# ThermocoupleADC.net
KiCad netlist of a schematic drawn in Altium Designer
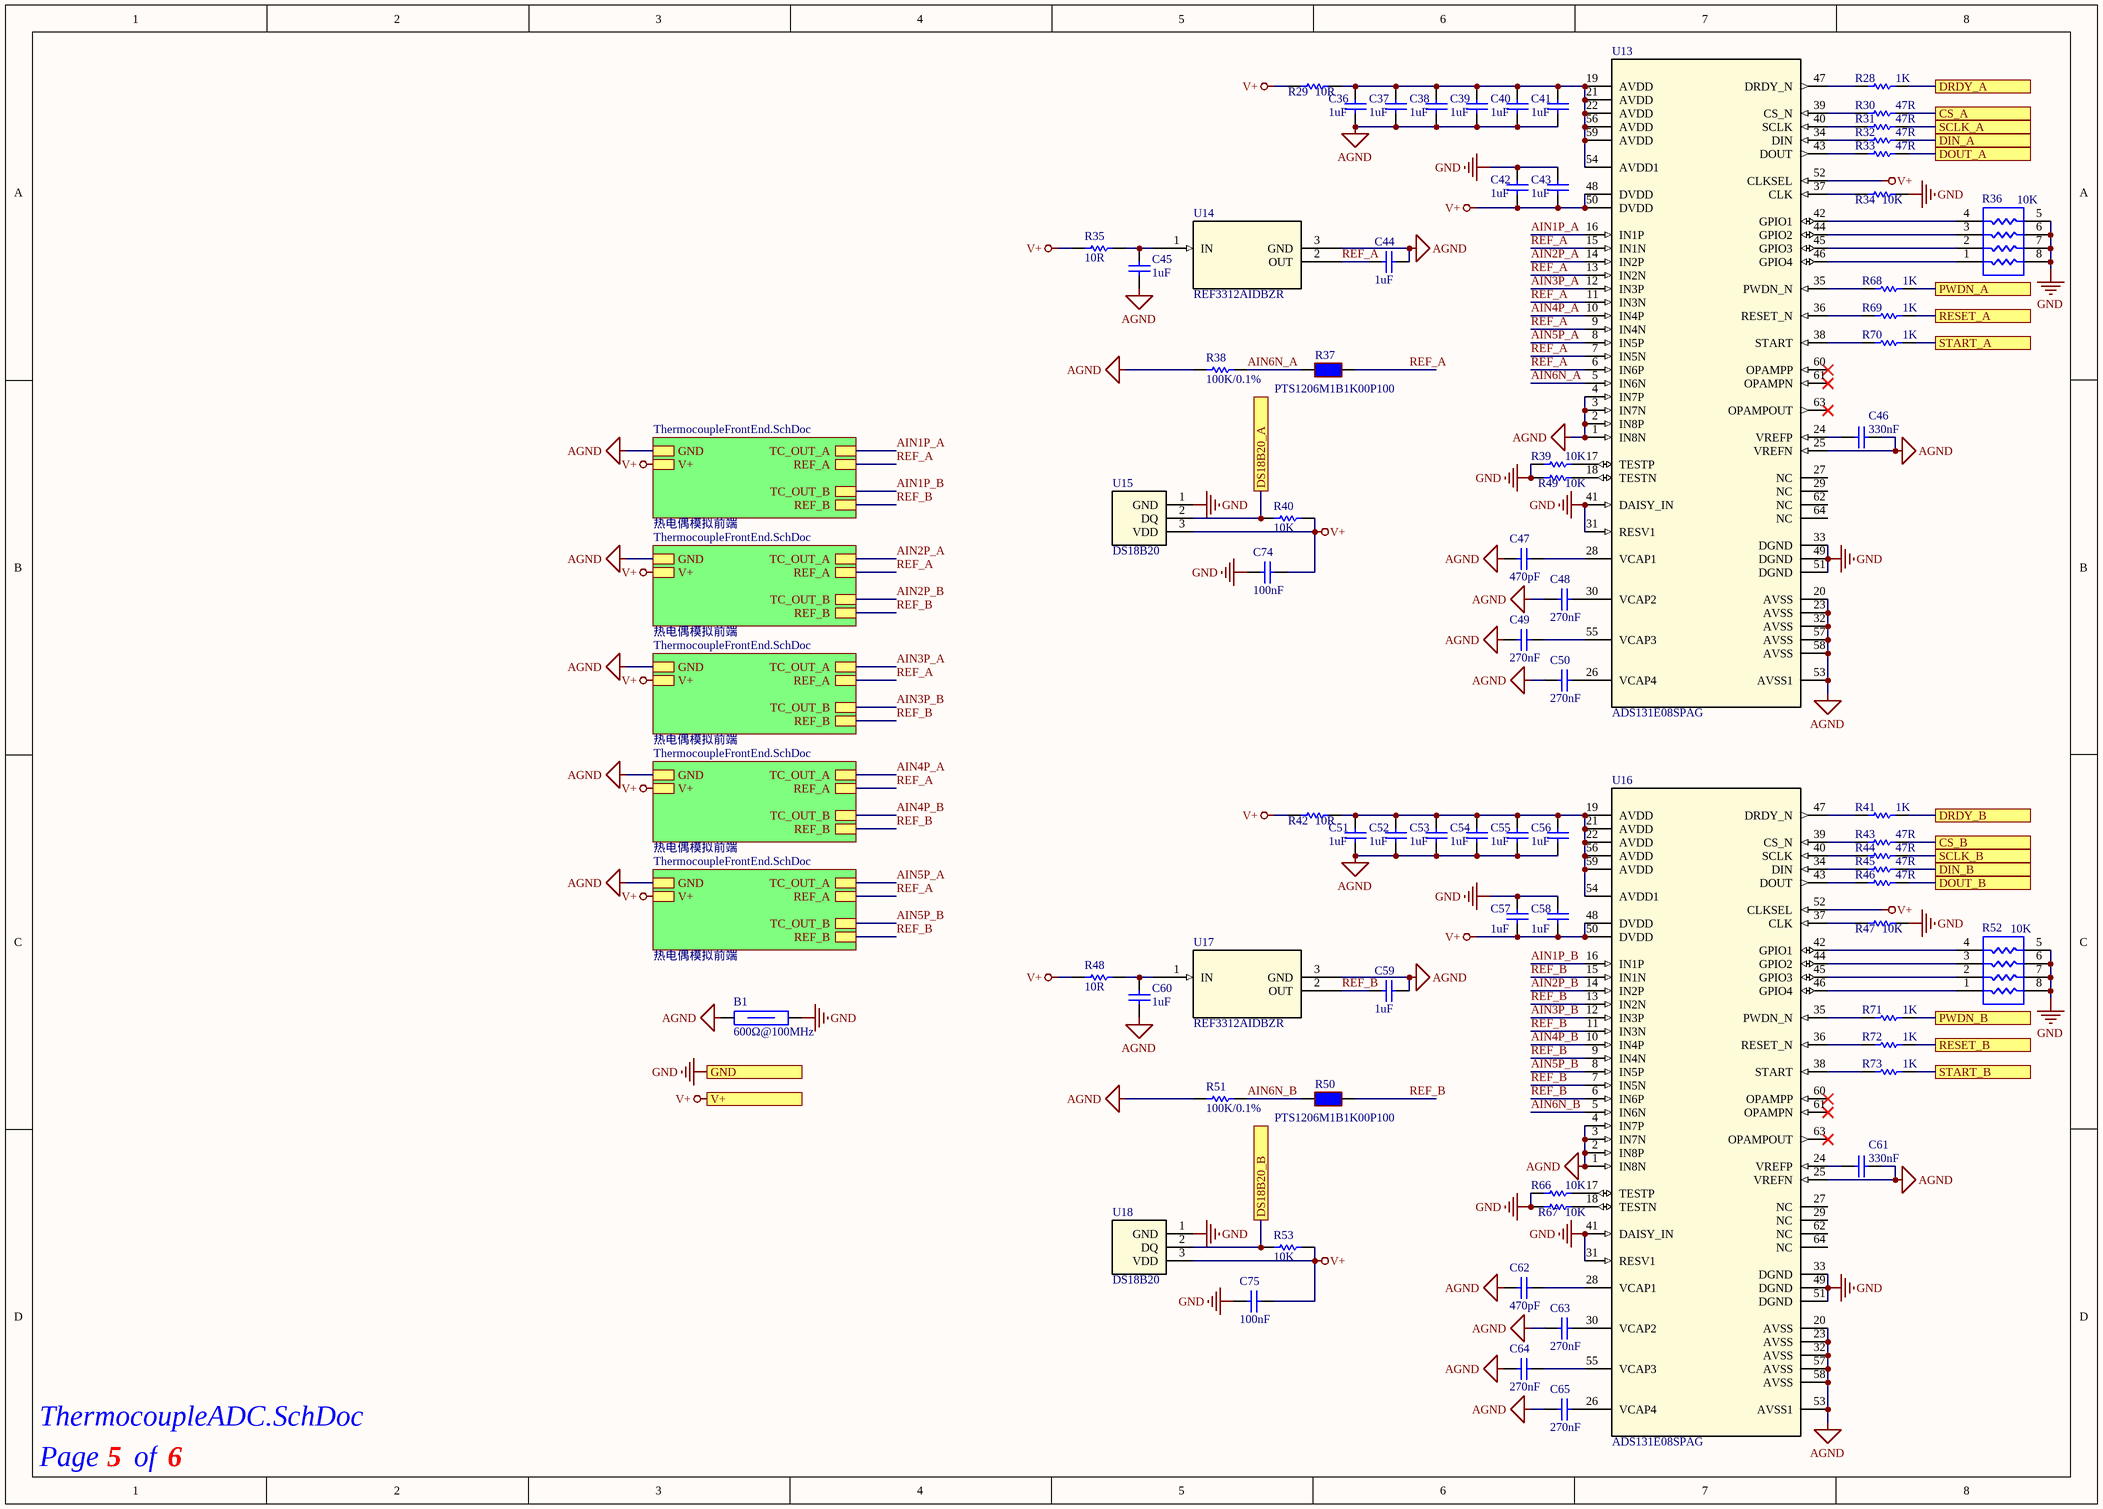
[diagram p0: ThermocoupleADC.SchDoc]

(export (version "E")
  (design (tool "Eeschema 10.0.6"))
  (components
    (comp (ref "B1")
      (value "600Ω@100MHz")
      (footprint "R0805_L")
      (description "600Ω @ 100MHz \r\n线路数 1 \r\n额定电流（最大） 600mA \r\n直流电阻（DCR）（最大） 210mΩ")
      (libsource (lib "00Lib") (part "600Ω@100MHz"))
    )
    (comp (ref "C36")
      (value "1uF")
      (footprint "R0603_C")
      (description "精度 ±10% \r\n容值 1uF \r\n额定电压 50V \r\n温漂系数（介质材料) X7R")
      (libsource (lib "00Lib") (part "1uF/0603/50V"))
    )
    (comp (ref "C37")
      (value "1uF")
      (footprint "R0603_C")
      (description "精度 ±10% \r\n容值 1uF \r\n额定电压 50V \r\n温漂系数（介质材料) X7R")
      (libsource (lib "00Lib") (part "1uF/0603/50V"))
    )
    (comp (ref "C38")
      (value "1uF")
      (footprint "R0603_C")
      (description "精度 ±10% \r\n容值 1uF \r\n额定电压 50V \r\n温漂系数（介质材料) X7R")
      (libsource (lib "00Lib") (part "1uF/0603/50V"))
    )
    (comp (ref "C39")
      (value "1uF")
      (footprint "R0603_C")
      (description "精度 ±10% \r\n容值 1uF \r\n额定电压 50V \r\n温漂系数（介质材料) X7R")
      (libsource (lib "00Lib") (part "1uF/0603/50V"))
    )
    (comp (ref "C40")
      (value "1uF")
      (footprint "R0603_C")
      (description "精度 ±10% \r\n容值 1uF \r\n额定电压 50V \r\n温漂系数（介质材料) X7R")
      (libsource (lib "00Lib") (part "1uF/0603/50V"))
    )
    (comp (ref "C41")
      (value "1uF")
      (footprint "R0603_C")
      (description "精度 ±10% \r\n容值 1uF \r\n额定电压 50V \r\n温漂系数（介质材料) X7R")
      (libsource (lib "00Lib") (part "1uF/0603/50V"))
    )
    (comp (ref "C42")
      (value "1uF")
      (footprint "R0603_C")
      (description "精度 ±10% \r\n容值 1uF \r\n额定电压 50V \r\n温漂系数（介质材料) X7R")
      (libsource (lib "00Lib") (part "1uF/0603/50V"))
    )
    (comp (ref "C43")
      (value "1uF")
      (footprint "R0603_C")
      (description "精度 ±10% \r\n容值 1uF \r\n额定电压 50V \r\n温漂系数（介质材料) X7R")
      (libsource (lib "00Lib") (part "1uF/0603/50V"))
    )
    (comp (ref "C44")
      (value "1uF")
      (footprint "R0603_C")
      (description "精度 ±10% \r\n容值 1uF \r\n额定电压 50V \r\n温漂系数（介质材料) X7R")
      (libsource (lib "00Lib") (part "1uF/0603/50V"))
    )
    (comp (ref "C45")
      (value "1uF")
      (footprint "R0603_C")
      (description "精度 ±10% \r\n容值 1uF \r\n额定电压 50V \r\n温漂系数（介质材料) X7R")
      (libsource (lib "00Lib") (part "1uF/0603/50V"))
    )
    (comp (ref "C46")
      (value "330nF")
      (footprint "R0603_C")
      (description "精度 ±10% \r\n容值 330nF \r\n额定电压 25V \r\n温漂系数（介质材料) X7R")
      (libsource (lib "00Lib") (part "330nF/0603/25V"))
    )
    (comp (ref "C47")
      (value "470pF")
      (footprint "R0603_C")
      (description "精度 ±5% \r\n容值 470pF \r\n额定电压 50V \r\n温漂系数（介质材料) C0G")
      (libsource (lib "00Lib") (part "470pF/0603/50V"))
    )
    (comp (ref "C48")
      (value "270nF")
      (footprint "R0603_C")
      (description "精度 ±10% \r\n容值 270nF \r\n额定电压 50V \r\n温漂系数（介质材料) X7R")
      (libsource (lib "00Lib") (part "270nF/0603/50V"))
    )
    (comp (ref "C49")
      (value "270nF")
      (footprint "R0603_C")
      (description "精度 ±10% \r\n容值 270nF \r\n额定电压 50V \r\n温漂系数（介质材料) X7R")
      (libsource (lib "00Lib") (part "270nF/0603/50V"))
    )
    (comp (ref "C50")
      (value "270nF")
      (footprint "R0603_C")
      (description "精度 ±10% \r\n容值 270nF \r\n额定电压 50V \r\n温漂系数（介质材料) X7R")
      (libsource (lib "00Lib") (part "270nF/0603/50V"))
    )
    (comp (ref "C51")
      (value "1uF")
      (footprint "R0603_C")
      (description "精度 ±10% \r\n容值 1uF \r\n额定电压 50V \r\n温漂系数（介质材料) X7R")
      (libsource (lib "00Lib") (part "1uF/0603/50V"))
    )
    (comp (ref "C52")
      (value "1uF")
      (footprint "R0603_C")
      (description "精度 ±10% \r\n容值 1uF \r\n额定电压 50V \r\n温漂系数（介质材料) X7R")
      (libsource (lib "00Lib") (part "1uF/0603/50V"))
    )
    (comp (ref "C53")
      (value "1uF")
      (footprint "R0603_C")
      (description "精度 ±10% \r\n容值 1uF \r\n额定电压 50V \r\n温漂系数（介质材料) X7R")
      (libsource (lib "00Lib") (part "1uF/0603/50V"))
    )
    (comp (ref "C54")
      (value "1uF")
      (footprint "R0603_C")
      (description "精度 ±10% \r\n容值 1uF \r\n额定电压 50V \r\n温漂系数（介质材料) X7R")
      (libsource (lib "00Lib") (part "1uF/0603/50V"))
    )
    (comp (ref "C55")
      (value "1uF")
      (footprint "R0603_C")
      (description "精度 ±10% \r\n容值 1uF \r\n额定电压 50V \r\n温漂系数（介质材料) X7R")
      (libsource (lib "00Lib") (part "1uF/0603/50V"))
    )
    (comp (ref "C56")
      (value "1uF")
      (footprint "R0603_C")
      (description "精度 ±10% \r\n容值 1uF \r\n额定电压 50V \r\n温漂系数（介质材料) X7R")
      (libsource (lib "00Lib") (part "1uF/0603/50V"))
    )
    (comp (ref "C57")
      (value "1uF")
      (footprint "R0603_C")
      (description "精度 ±10% \r\n容值 1uF \r\n额定电压 50V \r\n温漂系数（介质材料) X7R")
      (libsource (lib "00Lib") (part "1uF/0603/50V"))
    )
    (comp (ref "C58")
      (value "1uF")
      (footprint "R0603_C")
      (description "精度 ±10% \r\n容值 1uF \r\n额定电压 50V \r\n温漂系数（介质材料) X7R")
      (libsource (lib "00Lib") (part "1uF/0603/50V"))
    )
    (comp (ref "C59")
      (value "1uF")
      (footprint "R0603_C")
      (description "精度 ±10% \r\n容值 1uF \r\n额定电压 50V \r\n温漂系数（介质材料) X7R")
      (libsource (lib "00Lib") (part "1uF/0603/50V"))
    )
    (comp (ref "C60")
      (value "1uF")
      (footprint "R0603_C")
      (description "精度 ±10% \r\n容值 1uF \r\n额定电压 50V \r\n温漂系数（介质材料) X7R")
      (libsource (lib "00Lib") (part "1uF/0603/50V"))
    )
    (comp (ref "C61")
      (value "330nF")
      (footprint "R0603_C")
      (description "精度 ±10% \r\n容值 330nF \r\n额定电压 25V \r\n温漂系数（介质材料) X7R")
      (libsource (lib "00Lib") (part "330nF/0603/25V"))
    )
    (comp (ref "C62")
      (value "470pF")
      (footprint "R0603_C")
      (description "精度 ±5% \r\n容值 470pF \r\n额定电压 50V \r\n温漂系数（介质材料) C0G")
      (libsource (lib "00Lib") (part "470pF/0603/50V"))
    )
    (comp (ref "C63")
      (value "270nF")
      (footprint "R0603_C")
      (description "精度 ±10% \r\n容值 270nF \r\n额定电压 50V \r\n温漂系数（介质材料) X7R")
      (libsource (lib "00Lib") (part "270nF/0603/50V"))
    )
    (comp (ref "C64")
      (value "270nF")
      (footprint "R0603_C")
      (description "精度 ±10% \r\n容值 270nF \r\n额定电压 50V \r\n温漂系数（介质材料) X7R")
      (libsource (lib "00Lib") (part "270nF/0603/50V"))
    )
    (comp (ref "C65")
      (value "270nF")
      (footprint "R0603_C")
      (description "精度 ±10% \r\n容值 270nF \r\n额定电压 50V \r\n温漂系数（介质材料) X7R")
      (libsource (lib "00Lib") (part "270nF/0603/50V"))
    )
    (comp (ref "C74")
      (value "100nF")
      (footprint "R0603_C")
      (description "精度 ±10% \r\n容值 100nF \r\n额定电压 50V \r\n温漂系数（介质材料) X7R")
      (libsource (lib "00Lib") (part "100nF/0603/50V"))
    )
    (comp (ref "C75")
      (value "100nF")
      (footprint "R0603_C")
      (description "精度 ±10% \r\n容值 100nF \r\n额定电压 50V \r\n温漂系数（介质材料) X7R")
      (libsource (lib "00Lib") (part "100nF/0603/50V"))
    )
    (comp (ref "R28")
      (value "1K")
      (footprint "R0603_R")
      (description "精度 ±1% \r\n温度系数 ±100ppm/℃ \r\n阻值 1kΩ \r\n功率 0.1W")
      (libsource (lib "00Lib") (part "1K/0603"))
    )
    (comp (ref "R29")
      (value "10R")
      (footprint "R0603_R")
      (description "精度 ±1% \r\n阻值 10Ω \r\n温度系数 ±100ppm/℃ \r\n功率 0.1W")
      (libsource (lib "00Lib") (part "10R/0603"))
    )
    (comp (ref "R30")
      (value "47R")
      (footprint "R0603_R")
      (description "精度 ±1% \r\n温度系数 ±100ppm/℃ \r\n阻值 47Ω \r\n功率 0.1W")
      (libsource (lib "00Lib") (part "47R/0603"))
    )
    (comp (ref "R31")
      (value "47R")
      (footprint "R0603_R")
      (description "精度 ±1% \r\n温度系数 ±100ppm/℃ \r\n阻值 47Ω \r\n功率 0.1W")
      (libsource (lib "00Lib") (part "47R/0603"))
    )
    (comp (ref "R32")
      (value "47R")
      (footprint "R0603_R")
      (description "精度 ±1% \r\n温度系数 ±100ppm/℃ \r\n阻值 47Ω \r\n功率 0.1W")
      (libsource (lib "00Lib") (part "47R/0603"))
    )
    (comp (ref "R33")
      (value "47R")
      (footprint "R0603_R")
      (description "精度 ±1% \r\n温度系数 ±100ppm/℃ \r\n阻值 47Ω \r\n功率 0.1W")
      (libsource (lib "00Lib") (part "47R/0603"))
    )
    (comp (ref "R34")
      (value "10K")
      (footprint "R0603_R")
      (description "精度 ±1% \r\n温度系数 ±100ppm/℃ \r\n阻值 10kΩ \r\n功率 0.1W")
      (libsource (lib "00Lib") (part "10K/0603"))
    )
    (comp (ref "R35")
      (value "10R")
      (footprint "R0603_R")
      (description "精度 ±1% \r\n阻值 10Ω \r\n温度系数 ±100ppm/℃ \r\n功率 0.1W")
      (libsource (lib "00Lib") (part "10R/0603"))
    )
    (comp (ref "R36")
      (value "10K")
      (footprint "R0603X4")
      (description "10K \r\n电阻器数 4 \r\n精度 ±1% \r\n安装类型 表面贴装 \r\n每元件功率 1/16W \r\n温度系数 ±200ppm/℃")
      (libsource (lib "00Lib") (part "10K/0603X4"))
    )
    (comp (ref "R37")
      (value "PTS1206M1B1K00P100")
      (footprint "R1206_R")
      (description "PT1000")
      (libsource (lib "00Lib") (part "PTS1206M1B1K00P100"))
    )
    (comp (ref "R38")
      (value "100K/0.1%")
      (footprint "R0603_R")
      (description "精度 ±0.1% \r\n阻值 100kΩ \r\n功率 0.1W")
      (libsource (lib "00Lib") (part "100K/0603/0.1%"))
    )
    (comp (ref "R39")
      (value "10K")
      (footprint "R0603_R")
      (description "精度 ±1% \r\n温度系数 ±100ppm/℃ \r\n阻值 10kΩ \r\n功率 0.1W")
      (libsource (lib "00Lib") (part "10K/0603"))
    )
    (comp (ref "R40")
      (value "10K")
      (footprint "R0603_R")
      (description "精度 ±1% \r\n温度系数 ±100ppm/℃ \r\n阻值 10kΩ \r\n功率 0.1W")
      (libsource (lib "00Lib") (part "10K/0603"))
    )
    (comp (ref "R41")
      (value "1K")
      (footprint "R0603_R")
      (description "精度 ±1% \r\n温度系数 ±100ppm/℃ \r\n阻值 1kΩ \r\n功率 0.1W")
      (libsource (lib "00Lib") (part "1K/0603"))
    )
    (comp (ref "R42")
      (value "10R")
      (footprint "R0603_R")
      (description "精度 ±1% \r\n阻值 10Ω \r\n温度系数 ±100ppm/℃ \r\n功率 0.1W")
      (libsource (lib "00Lib") (part "10R/0603"))
    )
    (comp (ref "R43")
      (value "47R")
      (footprint "R0603_R")
      (description "精度 ±1% \r\n温度系数 ±100ppm/℃ \r\n阻值 47Ω \r\n功率 0.1W")
      (libsource (lib "00Lib") (part "47R/0603"))
    )
    (comp (ref "R44")
      (value "47R")
      (footprint "R0603_R")
      (description "精度 ±1% \r\n温度系数 ±100ppm/℃ \r\n阻值 47Ω \r\n功率 0.1W")
      (libsource (lib "00Lib") (part "47R/0603"))
    )
    (comp (ref "R45")
      (value "47R")
      (footprint "R0603_R")
      (description "精度 ±1% \r\n温度系数 ±100ppm/℃ \r\n阻值 47Ω \r\n功率 0.1W")
      (libsource (lib "00Lib") (part "47R/0603"))
    )
    (comp (ref "R46")
      (value "47R")
      (footprint "R0603_R")
      (description "精度 ±1% \r\n温度系数 ±100ppm/℃ \r\n阻值 47Ω \r\n功率 0.1W")
      (libsource (lib "00Lib") (part "47R/0603"))
    )
    (comp (ref "R47")
      (value "10K")
      (footprint "R0603_R")
      (description "精度 ±1% \r\n温度系数 ±100ppm/℃ \r\n阻值 10kΩ \r\n功率 0.1W")
      (libsource (lib "00Lib") (part "10K/0603"))
    )
    (comp (ref "R48")
      (value "10R")
      (footprint "R0603_R")
      (description "精度 ±1% \r\n阻值 10Ω \r\n温度系数 ±100ppm/℃ \r\n功率 0.1W")
      (libsource (lib "00Lib") (part "10R/0603"))
    )
    (comp (ref "R49")
      (value "10K")
      (footprint "R0603_R")
      (description "精度 ±1% \r\n温度系数 ±100ppm/℃ \r\n阻值 10kΩ \r\n功率 0.1W")
      (libsource (lib "00Lib") (part "10K/0603"))
    )
    (comp (ref "R50")
      (value "PTS1206M1B1K00P100")
      (footprint "R1206_R")
      (description "PT1000")
      (libsource (lib "00Lib") (part "PTS1206M1B1K00P100"))
    )
    (comp (ref "R51")
      (value "100K/0.1%")
      (footprint "R0603_R")
      (description "精度 ±0.1% \r\n阻值 100kΩ \r\n功率 0.1W")
      (libsource (lib "00Lib") (part "100K/0603/0.1%"))
    )
    (comp (ref "R52")
      (value "10K")
      (footprint "R0603X4")
      (description "10K \r\n电阻器数 4 \r\n精度 ±1% \r\n安装类型 表面贴装 \r\n每元件功率 1/16W \r\n温度系数 ±200ppm/℃")
      (libsource (lib "00Lib") (part "10K/0603X4"))
    )
    (comp (ref "R53")
      (value "10K")
      (footprint "R0603_R")
      (description "精度 ±1% \r\n温度系数 ±100ppm/℃ \r\n阻值 10kΩ \r\n功率 0.1W")
      (libsource (lib "00Lib") (part "10K/0603"))
    )
    (comp (ref "R66")
      (value "10K")
      (footprint "R0603_R")
      (description "精度 ±1% \r\n温度系数 ±100ppm/℃ \r\n阻值 10kΩ \r\n功率 0.1W")
      (libsource (lib "00Lib") (part "10K/0603"))
    )
    (comp (ref "R67")
      (value "10K")
      (footprint "R0603_R")
      (description "精度 ±1% \r\n温度系数 ±100ppm/℃ \r\n阻值 10kΩ \r\n功率 0.1W")
      (libsource (lib "00Lib") (part "10K/0603"))
    )
    (comp (ref "R68")
      (value "1K")
      (footprint "R0603_R")
      (description "精度 ±1% \r\n温度系数 ±100ppm/℃ \r\n阻值 1kΩ \r\n功率 0.1W")
      (libsource (lib "00Lib") (part "1K/0603"))
    )
    (comp (ref "R69")
      (value "1K")
      (footprint "R0603_R")
      (description "精度 ±1% \r\n温度系数 ±100ppm/℃ \r\n阻值 1kΩ \r\n功率 0.1W")
      (libsource (lib "00Lib") (part "1K/0603"))
    )
    (comp (ref "R70")
      (value "1K")
      (footprint "R0603_R")
      (description "精度 ±1% \r\n温度系数 ±100ppm/℃ \r\n阻值 1kΩ \r\n功率 0.1W")
      (libsource (lib "00Lib") (part "1K/0603"))
    )
    (comp (ref "R71")
      (value "1K")
      (footprint "R0603_R")
      (description "精度 ±1% \r\n温度系数 ±100ppm/℃ \r\n阻值 1kΩ \r\n功率 0.1W")
      (libsource (lib "00Lib") (part "1K/0603"))
    )
    (comp (ref "R72")
      (value "1K")
      (footprint "R0603_R")
      (description "精度 ±1% \r\n温度系数 ±100ppm/℃ \r\n阻值 1kΩ \r\n功率 0.1W")
      (libsource (lib "00Lib") (part "1K/0603"))
    )
    (comp (ref "R73")
      (value "1K")
      (footprint "R0603_R")
      (description "精度 ±1% \r\n温度系数 ±100ppm/℃ \r\n阻值 1kΩ \r\n功率 0.1W")
      (libsource (lib "00Lib") (part "1K/0603"))
    )
    (comp (ref "U13")
      (value "ADS131E08SPAG")
      (footprint "TQFP-64")
      (libsource (lib "00Lib") (part "ADS131E08SPAG"))
    )
    (comp (ref "U14")
      (value "REF3312AIDBZR")
      (footprint "SOT-23(SOT-23-3)")
      (description "电压参考")
      (libsource (lib "00Lib") (part "REF3312AIDBZR"))
    )
    (comp (ref "U15")
      (value "DS18B20")
      (footprint "TO-92")
      (description "温度传感器2.5~5.5V")
      (libsource (lib "00Lib") (part "DS18B20"))
    )
    (comp (ref "U16")
      (value "ADS131E08SPAG")
      (footprint "TQFP-64")
      (libsource (lib "00Lib") (part "ADS131E08SPAG"))
    )
    (comp (ref "U17")
      (value "REF3312AIDBZR")
      (footprint "SOT-23(SOT-23-3)")
      (description "电压参考")
      (libsource (lib "00Lib") (part "REF3312AIDBZR"))
    )
    (comp (ref "U18")
      (value "DS18B20")
      (footprint "TO-92")
      (description "温度传感器2.5~5.5V")
      (libsource (lib "00Lib") (part "DS18B20"))
    )
  )
  (nets
    (net (code "1") (name "/AIN1P_A") (class "Default")
      (node (ref "U13") (pin "16") (pinfunction "IN1P_16") (pintype "input"))
    )
    (net (code "2") (name "/AIN1P_B") (class "Default")
      (node (ref "U16") (pin "16") (pinfunction "IN1P_16") (pintype "input"))
    )
    (net (code "3") (name "/AIN2P_A") (class "Default")
      (node (ref "U13") (pin "14") (pinfunction "IN2P_14") (pintype "input"))
    )
    (net (code "4") (name "/AIN2P_B") (class "Default")
      (node (ref "U16") (pin "14") (pinfunction "IN2P_14") (pintype "input"))
    )
    (net (code "5") (name "/AIN3P_A") (class "Default")
      (node (ref "U13") (pin "12") (pinfunction "IN3P_12") (pintype "input"))
    )
    (net (code "6") (name "/AIN3P_B") (class "Default")
      (node (ref "U16") (pin "12") (pinfunction "IN3P_12") (pintype "input"))
    )
    (net (code "7") (name "/AIN4P_A") (class "Default")
      (node (ref "U13") (pin "10") (pinfunction "IN4P_10") (pintype "input"))
    )
    (net (code "8") (name "/AIN4P_B") (class "Default")
      (node (ref "U16") (pin "10") (pinfunction "IN4P_10") (pintype "input"))
    )
    (net (code "9") (name "/AIN5P_A") (class "Default")
      (node (ref "U13") (pin "8") (pinfunction "IN5P_8") (pintype "input"))
    )
    (net (code "10") (name "/AIN5P_B") (class "Default")
      (node (ref "U16") (pin "8") (pinfunction "IN5P_8") (pintype "input"))
    )
    (net (code "11") (name "/AIN6N_A") (class "Default")
      (node (ref "R37") (pin "2") (pinfunction "2_2") (pintype "passive"))
      (node (ref "R38") (pin "1") (pinfunction "1_1") (pintype "passive"))
      (node (ref "U13") (pin "5") (pinfunction "IN6N_5") (pintype "input"))
    )
    (net (code "12") (name "/AIN6N_B") (class "Default")
      (node (ref "R50") (pin "2") (pinfunction "2_2") (pintype "passive"))
      (node (ref "R51") (pin "1") (pinfunction "1_1") (pintype "passive"))
      (node (ref "U16") (pin "5") (pinfunction "IN6N_5") (pintype "input"))
    )
    (net (code "13") (name "/CS_A") (class "Default")
      (node (ref "R30") (pin "2") (pinfunction "2_2") (pintype "passive"))
    )
    (net (code "14") (name "/CS_B") (class "Default")
      (node (ref "R43") (pin "2") (pinfunction "2_2") (pintype "passive"))
    )
    (net (code "15") (name "/DIN_A") (class "Default")
      (node (ref "R32") (pin "2") (pinfunction "2_2") (pintype "passive"))
    )
    (net (code "16") (name "/DIN_B") (class "Default")
      (node (ref "R45") (pin "2") (pinfunction "2_2") (pintype "passive"))
    )
    (net (code "17") (name "/DOUT_A") (class "Default")
      (node (ref "R33") (pin "2") (pinfunction "2_2") (pintype "passive"))
    )
    (net (code "18") (name "/DOUT_B") (class "Default")
      (node (ref "R46") (pin "2") (pinfunction "2_2") (pintype "passive"))
    )
    (net (code "19") (name "/DRDY_A") (class "Default")
      (node (ref "R28") (pin "2") (pinfunction "2_2") (pintype "passive"))
    )
    (net (code "20") (name "/DRDY_B") (class "Default")
      (node (ref "R41") (pin "2") (pinfunction "2_2") (pintype "passive"))
    )
    (net (code "21") (name "/DS18B20_A") (class "Default")
      (node (ref "R40") (pin "1") (pinfunction "1_1") (pintype "passive"))
      (node (ref "U15") (pin "2") (pinfunction "DQ_2") (pintype "power_in"))
    )
    (net (code "22") (name "/DS18B20_B") (class "Default")
      (node (ref "R53") (pin "1") (pinfunction "1_1") (pintype "passive"))
      (node (ref "U18") (pin "2") (pinfunction "DQ_2") (pintype "power_in"))
    )
    (net (code "23") (name "/PWDN_A") (class "Default")
      (node (ref "R68") (pin "2") (pinfunction "2_2") (pintype "passive"))
    )
    (net (code "24") (name "/PWDN_B") (class "Default")
      (node (ref "R71") (pin "2") (pinfunction "2_2") (pintype "passive"))
    )
    (net (code "25") (name "/REF_A") (class "Default")
      (node (ref "C44") (pin "2") (pinfunction "2_2") (pintype "passive"))
      (node (ref "R37") (pin "1") (pinfunction "1_1") (pintype "passive"))
      (node (ref "U13") (pin "11") (pinfunction "IN3N_11") (pintype "input"))
      (node (ref "U13") (pin "13") (pinfunction "IN2N_13") (pintype "input"))
      (node (ref "U13") (pin "15") (pinfunction "IN1N_15") (pintype "input"))
      (node (ref "U13") (pin "6") (pinfunction "IN6P_6") (pintype "input"))
      (node (ref "U13") (pin "7") (pinfunction "IN5N_7") (pintype "input"))
      (node (ref "U13") (pin "9") (pinfunction "IN4N_9") (pintype "input"))
      (node (ref "U14") (pin "2") (pinfunction "OUT_2") (pintype "power_in"))
    )
    (net (code "26") (name "/REF_B") (class "Default")
      (node (ref "C59") (pin "2") (pinfunction "2_2") (pintype "passive"))
      (node (ref "R50") (pin "1") (pinfunction "1_1") (pintype "passive"))
      (node (ref "U16") (pin "11") (pinfunction "IN3N_11") (pintype "input"))
      (node (ref "U16") (pin "13") (pinfunction "IN2N_13") (pintype "input"))
      (node (ref "U16") (pin "15") (pinfunction "IN1N_15") (pintype "input"))
      (node (ref "U16") (pin "6") (pinfunction "IN6P_6") (pintype "input"))
      (node (ref "U16") (pin "7") (pinfunction "IN5N_7") (pintype "input"))
      (node (ref "U16") (pin "9") (pinfunction "IN4N_9") (pintype "input"))
      (node (ref "U17") (pin "2") (pinfunction "OUT_2") (pintype "power_in"))
    )
    (net (code "27") (name "/RESET_A") (class "Default")
      (node (ref "R69") (pin "2") (pinfunction "2_2") (pintype "passive"))
    )
    (net (code "28") (name "/RESET_B") (class "Default")
      (node (ref "R72") (pin "2") (pinfunction "2_2") (pintype "passive"))
    )
    (net (code "29") (name "/SCLK_A") (class "Default")
      (node (ref "R31") (pin "2") (pinfunction "2_2") (pintype "passive"))
    )
    (net (code "30") (name "/SCLK_B") (class "Default")
      (node (ref "R44") (pin "2") (pinfunction "2_2") (pintype "passive"))
    )
    (net (code "31") (name "/START_A") (class "Default")
      (node (ref "R70") (pin "2") (pinfunction "2_2") (pintype "passive"))
    )
    (net (code "32") (name "/START_B") (class "Default")
      (node (ref "R73") (pin "2") (pinfunction "2_2") (pintype "passive"))
    )
    (net (code "33") (name "AGND") (class "Default")
      (node (ref "B1") (pin "2") (pinfunction "2_2") (pintype "passive"))
      (node (ref "C36") (pin "1") (pinfunction "1_1") (pintype "passive"))
      (node (ref "C37") (pin "1") (pinfunction "1_1") (pintype "passive"))
      (node (ref "C38") (pin "1") (pinfunction "1_1") (pintype "passive"))
      (node (ref "C39") (pin "1") (pinfunction "1_1") (pintype "passive"))
      (node (ref "C40") (pin "1") (pinfunction "1_1") (pintype "passive"))
      (node (ref "C41") (pin "1") (pinfunction "1_1") (pintype "passive"))
      (node (ref "C44") (pin "1") (pinfunction "1_1") (pintype "passive"))
      (node (ref "C45") (pin "1") (pinfunction "1_1") (pintype "passive"))
      (node (ref "C46") (pin "1") (pinfunction "1_1") (pintype "passive"))
      (node (ref "C47") (pin "2") (pinfunction "2_2") (pintype "passive"))
      (node (ref "C48") (pin "2") (pinfunction "2_2") (pintype "passive"))
      (node (ref "C49") (pin "2") (pinfunction "2_2") (pintype "passive"))
      (node (ref "C50") (pin "2") (pinfunction "2_2") (pintype "passive"))
      (node (ref "C51") (pin "1") (pinfunction "1_1") (pintype "passive"))
      (node (ref "C52") (pin "1") (pinfunction "1_1") (pintype "passive"))
      (node (ref "C53") (pin "1") (pinfunction "1_1") (pintype "passive"))
      (node (ref "C54") (pin "1") (pinfunction "1_1") (pintype "passive"))
      (node (ref "C55") (pin "1") (pinfunction "1_1") (pintype "passive"))
      (node (ref "C56") (pin "1") (pinfunction "1_1") (pintype "passive"))
      (node (ref "C59") (pin "1") (pinfunction "1_1") (pintype "passive"))
      (node (ref "C60") (pin "1") (pinfunction "1_1") (pintype "passive"))
      (node (ref "C61") (pin "1") (pinfunction "1_1") (pintype "passive"))
      (node (ref "C62") (pin "2") (pinfunction "2_2") (pintype "passive"))
      (node (ref "C63") (pin "2") (pinfunction "2_2") (pintype "passive"))
      (node (ref "C64") (pin "2") (pinfunction "2_2") (pintype "passive"))
      (node (ref "C65") (pin "2") (pinfunction "2_2") (pintype "passive"))
      (node (ref "R38") (pin "2") (pinfunction "2_2") (pintype "passive"))
      (node (ref "R51") (pin "2") (pinfunction "2_2") (pintype "passive"))
      (node (ref "U13") (pin "1") (pinfunction "IN8N_1") (pintype "input"))
      (node (ref "U13") (pin "2") (pinfunction "IN8P_2") (pintype "input"))
      (node (ref "U13") (pin "20") (pinfunction "AVSS_20") (pintype "power_in"))
      (node (ref "U13") (pin "23") (pinfunction "AVSS_23") (pintype "power_in"))
      (node (ref "U13") (pin "25") (pinfunction "VREFN_25") (pintype "input"))
      (node (ref "U13") (pin "3") (pinfunction "IN7N_3") (pintype "input"))
      (node (ref "U13") (pin "32") (pinfunction "AVSS_32") (pintype "power_in"))
      (node (ref "U13") (pin "4") (pinfunction "IN7P_4") (pintype "input"))
      (node (ref "U13") (pin "53") (pinfunction "AVSS1_53") (pintype "power_in"))
      (node (ref "U13") (pin "57") (pinfunction "AVSS_57") (pintype "power_in"))
      (node (ref "U13") (pin "58") (pinfunction "AVSS_58") (pintype "power_in"))
      (node (ref "U14") (pin "3") (pinfunction "GND_3") (pintype "power_in"))
      (node (ref "U16") (pin "1") (pinfunction "IN8N_1") (pintype "input"))
      (node (ref "U16") (pin "2") (pinfunction "IN8P_2") (pintype "input"))
      (node (ref "U16") (pin "20") (pinfunction "AVSS_20") (pintype "power_in"))
      (node (ref "U16") (pin "23") (pinfunction "AVSS_23") (pintype "power_in"))
      (node (ref "U16") (pin "25") (pinfunction "VREFN_25") (pintype "input"))
      (node (ref "U16") (pin "3") (pinfunction "IN7N_3") (pintype "input"))
      (node (ref "U16") (pin "32") (pinfunction "AVSS_32") (pintype "power_in"))
      (node (ref "U16") (pin "4") (pinfunction "IN7P_4") (pintype "input"))
      (node (ref "U16") (pin "53") (pinfunction "AVSS1_53") (pintype "power_in"))
      (node (ref "U16") (pin "57") (pinfunction "AVSS_57") (pintype "power_in"))
      (node (ref "U16") (pin "58") (pinfunction "AVSS_58") (pintype "power_in"))
      (node (ref "U17") (pin "3") (pinfunction "GND_3") (pintype "power_in"))
    )
    (net (code "34") (name "GND") (class "Default")
      (node (ref "B1") (pin "1") (pinfunction "1_1") (pintype "passive"))
      (node (ref "C42") (pin "2") (pinfunction "2_2") (pintype "passive"))
      (node (ref "C43") (pin "2") (pinfunction "2_2") (pintype "passive"))
      (node (ref "C57") (pin "2") (pinfunction "2_2") (pintype "passive"))
      (node (ref "C58") (pin "2") (pinfunction "2_2") (pintype "passive"))
      (node (ref "C74") (pin "2") (pinfunction "2_2") (pintype "passive"))
      (node (ref "C75") (pin "2") (pinfunction "2_2") (pintype "passive"))
      (node (ref "R34") (pin "2") (pinfunction "2_2") (pintype "passive"))
      (node (ref "R36") (pin "5") (pinfunction "5_5") (pintype "passive"))
      (node (ref "R36") (pin "6") (pinfunction "6_6") (pintype "passive"))
      (node (ref "R36") (pin "7") (pinfunction "7_7") (pintype "passive"))
      (node (ref "R36") (pin "8") (pinfunction "8_8") (pintype "passive"))
      (node (ref "R39") (pin "2") (pinfunction "2_2") (pintype "passive"))
      (node (ref "R47") (pin "2") (pinfunction "2_2") (pintype "passive"))
      (node (ref "R49") (pin "2") (pinfunction "2_2") (pintype "passive"))
      (node (ref "R52") (pin "5") (pinfunction "5_5") (pintype "passive"))
      (node (ref "R52") (pin "6") (pinfunction "6_6") (pintype "passive"))
      (node (ref "R52") (pin "7") (pinfunction "7_7") (pintype "passive"))
      (node (ref "R52") (pin "8") (pinfunction "8_8") (pintype "passive"))
      (node (ref "R66") (pin "2") (pinfunction "2_2") (pintype "passive"))
      (node (ref "R67") (pin "2") (pinfunction "2_2") (pintype "passive"))
      (node (ref "U13") (pin "31") (pinfunction "RESV1_31") (pintype "input"))
      (node (ref "U13") (pin "33") (pinfunction "DGND_33") (pintype "power_in"))
      (node (ref "U13") (pin "41") (pinfunction "DAISY_IN_41") (pintype "input"))
      (node (ref "U13") (pin "49") (pinfunction "DGND_49") (pintype "power_in"))
      (node (ref "U13") (pin "51") (pinfunction "DGND_51") (pintype "power_in"))
      (node (ref "U15") (pin "1") (pinfunction "GND_1") (pintype "power_in"))
      (node (ref "U16") (pin "31") (pinfunction "RESV1_31") (pintype "input"))
      (node (ref "U16") (pin "33") (pinfunction "DGND_33") (pintype "power_in"))
      (node (ref "U16") (pin "41") (pinfunction "DAISY_IN_41") (pintype "input"))
      (node (ref "U16") (pin "49") (pinfunction "DGND_49") (pintype "power_in"))
      (node (ref "U16") (pin "51") (pinfunction "DGND_51") (pintype "power_in"))
      (node (ref "U18") (pin "1") (pinfunction "GND_1") (pintype "power_in"))
    )
    (net (code "35") (name "Net-(U13-AVDD1)") (class "Default")
      (node (ref "C36") (pin "2") (pinfunction "2_2") (pintype "passive"))
      (node (ref "C37") (pin "2") (pinfunction "2_2") (pintype "passive"))
      (node (ref "C38") (pin "2") (pinfunction "2_2") (pintype "passive"))
      (node (ref "C39") (pin "2") (pinfunction "2_2") (pintype "passive"))
      (node (ref "C40") (pin "2") (pinfunction "2_2") (pintype "passive"))
      (node (ref "C41") (pin "2") (pinfunction "2_2") (pintype "passive"))
      (node (ref "R29") (pin "2") (pinfunction "2_2") (pintype "passive"))
      (node (ref "U13") (pin "19") (pinfunction "AVDD_19") (pintype "power_in"))
      (node (ref "U13") (pin "21") (pinfunction "AVDD_21") (pintype "power_in"))
      (node (ref "U13") (pin "22") (pinfunction "AVDD_22") (pintype "power_in"))
      (node (ref "U13") (pin "54") (pinfunction "AVDD1_54") (pintype "power_in"))
      (node (ref "U13") (pin "56") (pinfunction "AVDD_56") (pintype "power_in"))
      (node (ref "U13") (pin "59") (pinfunction "AVDD_59") (pintype "power_in"))
    )
    (net (code "36") (name "Net-(U13-CLK)") (class "Default")
      (node (ref "R34") (pin "1") (pinfunction "1_1") (pintype "passive"))
      (node (ref "U13") (pin "37") (pinfunction "CLK_37") (pintype "input"))
    )
    (net (code "37") (name "Net-(U13-CS_N)") (class "Default")
      (node (ref "R30") (pin "1") (pinfunction "1_1") (pintype "passive"))
      (node (ref "U13") (pin "39") (pinfunction "CS_N_39") (pintype "input"))
    )
    (net (code "38") (name "Net-(U13-DIN)") (class "Default")
      (node (ref "R32") (pin "1") (pinfunction "1_1") (pintype "passive"))
      (node (ref "U13") (pin "34") (pinfunction "DIN_34") (pintype "input"))
    )
    (net (code "39") (name "Net-(U13-DOUT)") (class "Default")
      (node (ref "R33") (pin "1") (pinfunction "1_1") (pintype "passive"))
      (node (ref "U13") (pin "43") (pinfunction "DOUT_43") (pintype "output"))
    )
    (net (code "40") (name "Net-(U13-DRDY_N)") (class "Default")
      (node (ref "R28") (pin "1") (pinfunction "1_1") (pintype "passive"))
      (node (ref "U13") (pin "47") (pinfunction "DRDY_N_47") (pintype "output"))
    )
    (net (code "41") (name "Net-(U13-GPIO1)") (class "Default")
      (node (ref "R36") (pin "4") (pinfunction "4_4") (pintype "passive"))
      (node (ref "U13") (pin "42") (pinfunction "GPIO1_42") (pintype "bidirectional"))
    )
    (net (code "42") (name "Net-(U13-GPIO2)") (class "Default")
      (node (ref "R36") (pin "3") (pinfunction "3_3") (pintype "passive"))
      (node (ref "U13") (pin "44") (pinfunction "GPIO2_44") (pintype "bidirectional"))
    )
    (net (code "43") (name "Net-(U13-GPIO3)") (class "Default")
      (node (ref "R36") (pin "2") (pinfunction "2_2") (pintype "passive"))
      (node (ref "U13") (pin "45") (pinfunction "GPIO3_45") (pintype "bidirectional"))
    )
    (net (code "44") (name "Net-(U13-GPIO4)") (class "Default")
      (node (ref "R36") (pin "1") (pinfunction "1_1") (pintype "passive"))
      (node (ref "U13") (pin "46") (pinfunction "GPIO4_46") (pintype "bidirectional"))
    )
    (net (code "45") (name "Net-(U13-PWDN_N)") (class "Default")
      (node (ref "R68") (pin "1") (pinfunction "1_1") (pintype "passive"))
      (node (ref "U13") (pin "35") (pinfunction "PWDN_N_35") (pintype "input"))
    )
    (net (code "46") (name "Net-(U13-RESET_N)") (class "Default")
      (node (ref "R69") (pin "1") (pinfunction "1_1") (pintype "passive"))
      (node (ref "U13") (pin "36") (pinfunction "RESET_N_36") (pintype "input"))
    )
    (net (code "47") (name "Net-(U13-SCLK)") (class "Default")
      (node (ref "R31") (pin "1") (pinfunction "1_1") (pintype "passive"))
      (node (ref "U13") (pin "40") (pinfunction "SCLK_40") (pintype "input"))
    )
    (net (code "48") (name "Net-(U13-START)") (class "Default")
      (node (ref "R70") (pin "1") (pinfunction "1_1") (pintype "passive"))
      (node (ref "U13") (pin "38") (pinfunction "START_38") (pintype "input"))
    )
    (net (code "49") (name "Net-(U13-TESTN)") (class "Default")
      (node (ref "R49") (pin "1") (pinfunction "1_1") (pintype "passive"))
      (node (ref "U13") (pin "18") (pinfunction "TESTN_18") (pintype "bidirectional"))
    )
    (net (code "50") (name "Net-(U13-TESTP)") (class "Default")
      (node (ref "R39") (pin "1") (pinfunction "1_1") (pintype "passive"))
      (node (ref "U13") (pin "17") (pinfunction "TESTP_17") (pintype "bidirectional"))
    )
    (net (code "51") (name "Net-(U13-VCAP1)") (class "Default")
      (node (ref "C47") (pin "1") (pinfunction "1_1") (pintype "passive"))
      (node (ref "U13") (pin "28") (pinfunction "VCAP1_28") (pintype "passive"))
    )
    (net (code "52") (name "Net-(U13-VCAP2)") (class "Default")
      (node (ref "C48") (pin "1") (pinfunction "1_1") (pintype "passive"))
      (node (ref "U13") (pin "30") (pinfunction "VCAP2_30") (pintype "passive"))
    )
    (net (code "53") (name "Net-(U13-VCAP3)") (class "Default")
      (node (ref "C49") (pin "1") (pinfunction "1_1") (pintype "passive"))
      (node (ref "U13") (pin "55") (pinfunction "VCAP3_55") (pintype "passive"))
    )
    (net (code "54") (name "Net-(U13-VCAP4)") (class "Default")
      (node (ref "C50") (pin "1") (pinfunction "1_1") (pintype "passive"))
      (node (ref "U13") (pin "26") (pinfunction "VCAP4_26") (pintype "passive"))
    )
    (net (code "55") (name "Net-(U13-VREFP)") (class "Default")
      (node (ref "C46") (pin "2") (pinfunction "2_2") (pintype "passive"))
      (node (ref "U13") (pin "24") (pinfunction "VREFP_24") (pintype "input"))
    )
    (net (code "56") (name "Net-(U14-IN)") (class "Default")
      (node (ref "C45") (pin "2") (pinfunction "2_2") (pintype "passive"))
      (node (ref "R35") (pin "2") (pinfunction "2_2") (pintype "passive"))
      (node (ref "U14") (pin "1") (pinfunction "IN_1") (pintype "input"))
    )
    (net (code "57") (name "Net-(U16-AVDD1)") (class "Default")
      (node (ref "C51") (pin "2") (pinfunction "2_2") (pintype "passive"))
      (node (ref "C52") (pin "2") (pinfunction "2_2") (pintype "passive"))
      (node (ref "C53") (pin "2") (pinfunction "2_2") (pintype "passive"))
      (node (ref "C54") (pin "2") (pinfunction "2_2") (pintype "passive"))
      (node (ref "C55") (pin "2") (pinfunction "2_2") (pintype "passive"))
      (node (ref "C56") (pin "2") (pinfunction "2_2") (pintype "passive"))
      (node (ref "R42") (pin "2") (pinfunction "2_2") (pintype "passive"))
      (node (ref "U16") (pin "19") (pinfunction "AVDD_19") (pintype "power_in"))
      (node (ref "U16") (pin "21") (pinfunction "AVDD_21") (pintype "power_in"))
      (node (ref "U16") (pin "22") (pinfunction "AVDD_22") (pintype "power_in"))
      (node (ref "U16") (pin "54") (pinfunction "AVDD1_54") (pintype "power_in"))
      (node (ref "U16") (pin "56") (pinfunction "AVDD_56") (pintype "power_in"))
      (node (ref "U16") (pin "59") (pinfunction "AVDD_59") (pintype "power_in"))
    )
    (net (code "58") (name "Net-(U16-CLK)") (class "Default")
      (node (ref "R47") (pin "1") (pinfunction "1_1") (pintype "passive"))
      (node (ref "U16") (pin "37") (pinfunction "CLK_37") (pintype "input"))
    )
    (net (code "59") (name "Net-(U16-CS_N)") (class "Default")
      (node (ref "R43") (pin "1") (pinfunction "1_1") (pintype "passive"))
      (node (ref "U16") (pin "39") (pinfunction "CS_N_39") (pintype "input"))
    )
    (net (code "60") (name "Net-(U16-DIN)") (class "Default")
      (node (ref "R45") (pin "1") (pinfunction "1_1") (pintype "passive"))
      (node (ref "U16") (pin "34") (pinfunction "DIN_34") (pintype "input"))
    )
    (net (code "61") (name "Net-(U16-DOUT)") (class "Default")
      (node (ref "R46") (pin "1") (pinfunction "1_1") (pintype "passive"))
      (node (ref "U16") (pin "43") (pinfunction "DOUT_43") (pintype "output"))
    )
    (net (code "62") (name "Net-(U16-DRDY_N)") (class "Default")
      (node (ref "R41") (pin "1") (pinfunction "1_1") (pintype "passive"))
      (node (ref "U16") (pin "47") (pinfunction "DRDY_N_47") (pintype "output"))
    )
    (net (code "63") (name "Net-(U16-GPIO1)") (class "Default")
      (node (ref "R52") (pin "4") (pinfunction "4_4") (pintype "passive"))
      (node (ref "U16") (pin "42") (pinfunction "GPIO1_42") (pintype "bidirectional"))
    )
    (net (code "64") (name "Net-(U16-GPIO2)") (class "Default")
      (node (ref "R52") (pin "3") (pinfunction "3_3") (pintype "passive"))
      (node (ref "U16") (pin "44") (pinfunction "GPIO2_44") (pintype "bidirectional"))
    )
    (net (code "65") (name "Net-(U16-GPIO3)") (class "Default")
      (node (ref "R52") (pin "2") (pinfunction "2_2") (pintype "passive"))
      (node (ref "U16") (pin "45") (pinfunction "GPIO3_45") (pintype "bidirectional"))
    )
    (net (code "66") (name "Net-(U16-GPIO4)") (class "Default")
      (node (ref "R52") (pin "1") (pinfunction "1_1") (pintype "passive"))
      (node (ref "U16") (pin "46") (pinfunction "GPIO4_46") (pintype "bidirectional"))
    )
    (net (code "67") (name "Net-(U16-PWDN_N)") (class "Default")
      (node (ref "R71") (pin "1") (pinfunction "1_1") (pintype "passive"))
      (node (ref "U16") (pin "35") (pinfunction "PWDN_N_35") (pintype "input"))
    )
    (net (code "68") (name "Net-(U16-RESET_N)") (class "Default")
      (node (ref "R72") (pin "1") (pinfunction "1_1") (pintype "passive"))
      (node (ref "U16") (pin "36") (pinfunction "RESET_N_36") (pintype "input"))
    )
    (net (code "69") (name "Net-(U16-SCLK)") (class "Default")
      (node (ref "R44") (pin "1") (pinfunction "1_1") (pintype "passive"))
      (node (ref "U16") (pin "40") (pinfunction "SCLK_40") (pintype "input"))
    )
    (net (code "70") (name "Net-(U16-START)") (class "Default")
      (node (ref "R73") (pin "1") (pinfunction "1_1") (pintype "passive"))
      (node (ref "U16") (pin "38") (pinfunction "START_38") (pintype "input"))
    )
    (net (code "71") (name "Net-(U16-TESTN)") (class "Default")
      (node (ref "R67") (pin "1") (pinfunction "1_1") (pintype "passive"))
      (node (ref "U16") (pin "18") (pinfunction "TESTN_18") (pintype "bidirectional"))
    )
    (net (code "72") (name "Net-(U16-TESTP)") (class "Default")
      (node (ref "R66") (pin "1") (pinfunction "1_1") (pintype "passive"))
      (node (ref "U16") (pin "17") (pinfunction "TESTP_17") (pintype "bidirectional"))
    )
    (net (code "73") (name "Net-(U16-VCAP1)") (class "Default")
      (node (ref "C62") (pin "1") (pinfunction "1_1") (pintype "passive"))
      (node (ref "U16") (pin "28") (pinfunction "VCAP1_28") (pintype "passive"))
    )
    (net (code "74") (name "Net-(U16-VCAP2)") (class "Default")
      (node (ref "C63") (pin "1") (pinfunction "1_1") (pintype "passive"))
      (node (ref "U16") (pin "30") (pinfunction "VCAP2_30") (pintype "passive"))
    )
    (net (code "75") (name "Net-(U16-VCAP3)") (class "Default")
      (node (ref "C64") (pin "1") (pinfunction "1_1") (pintype "passive"))
      (node (ref "U16") (pin "55") (pinfunction "VCAP3_55") (pintype "passive"))
    )
    (net (code "76") (name "Net-(U16-VCAP4)") (class "Default")
      (node (ref "C65") (pin "1") (pinfunction "1_1") (pintype "passive"))
      (node (ref "U16") (pin "26") (pinfunction "VCAP4_26") (pintype "passive"))
    )
    (net (code "77") (name "Net-(U16-VREFP)") (class "Default")
      (node (ref "C61") (pin "2") (pinfunction "2_2") (pintype "passive"))
      (node (ref "U16") (pin "24") (pinfunction "VREFP_24") (pintype "input"))
    )
    (net (code "78") (name "Net-(U17-IN)") (class "Default")
      (node (ref "C60") (pin "2") (pinfunction "2_2") (pintype "passive"))
      (node (ref "R48") (pin "2") (pinfunction "2_2") (pintype "passive"))
      (node (ref "U17") (pin "1") (pinfunction "IN_1") (pintype "input"))
    )
    (net (code "79") (name "V+") (class "Default")
      (node (ref "C42") (pin "1") (pinfunction "1_1") (pintype "passive"))
      (node (ref "C43") (pin "1") (pinfunction "1_1") (pintype "passive"))
      (node (ref "C57") (pin "1") (pinfunction "1_1") (pintype "passive"))
      (node (ref "C58") (pin "1") (pinfunction "1_1") (pintype "passive"))
      (node (ref "C74") (pin "1") (pinfunction "1_1") (pintype "passive"))
      (node (ref "C75") (pin "1") (pinfunction "1_1") (pintype "passive"))
      (node (ref "R29") (pin "1") (pinfunction "1_1") (pintype "passive"))
      (node (ref "R35") (pin "1") (pinfunction "1_1") (pintype "passive"))
      (node (ref "R40") (pin "2") (pinfunction "2_2") (pintype "passive"))
      (node (ref "R42") (pin "1") (pinfunction "1_1") (pintype "passive"))
      (node (ref "R48") (pin "1") (pinfunction "1_1") (pintype "passive"))
      (node (ref "R53") (pin "2") (pinfunction "2_2") (pintype "passive"))
      (node (ref "U13") (pin "48") (pinfunction "DVDD_48") (pintype "power_in"))
      (node (ref "U13") (pin "50") (pinfunction "DVDD_50") (pintype "power_in"))
      (node (ref "U13") (pin "52") (pinfunction "CLKSEL_52") (pintype "input"))
      (node (ref "U15") (pin "3") (pinfunction "VDD_3") (pintype "passive"))
      (node (ref "U16") (pin "48") (pinfunction "DVDD_48") (pintype "power_in"))
      (node (ref "U16") (pin "50") (pinfunction "DVDD_50") (pintype "power_in"))
      (node (ref "U16") (pin "52") (pinfunction "CLKSEL_52") (pintype "input"))
      (node (ref "U18") (pin "3") (pinfunction "VDD_3") (pintype "passive"))
    )
    (net (code "80") (name "unconnected-(U13-NC-Pad27)") (class "Default")
      (node (ref "U13") (pin "27") (pinfunction "NC_27") (pintype "passive"))
    )
    (net (code "81") (name "unconnected-(U13-NC-Pad29)") (class "Default")
      (node (ref "U13") (pin "29") (pinfunction "NC_29") (pintype "passive"))
    )
    (net (code "82") (name "unconnected-(U13-NC-Pad62)") (class "Default")
      (node (ref "U13") (pin "62") (pinfunction "NC_62") (pintype "passive"))
    )
    (net (code "83") (name "unconnected-(U13-NC-Pad64)") (class "Default")
      (node (ref "U13") (pin "64") (pinfunction "NC_64") (pintype "passive"))
    )
    (net (code "84") (name "unconnected-(U13-OPAMPN-Pad61)") (class "Default")
      (node (ref "U13") (pin "61") (pinfunction "OPAMPN_61") (pintype "input+no_connect"))
    )
    (net (code "85") (name "unconnected-(U13-OPAMPOUT-Pad63)") (class "Default")
      (node (ref "U13") (pin "63") (pinfunction "OPAMPOUT_63") (pintype "output+no_connect"))
    )
    (net (code "86") (name "unconnected-(U13-OPAMPP-Pad60)") (class "Default")
      (node (ref "U13") (pin "60") (pinfunction "OPAMPP_60") (pintype "input+no_connect"))
    )
    (net (code "87") (name "unconnected-(U16-NC-Pad27)") (class "Default")
      (node (ref "U16") (pin "27") (pinfunction "NC_27") (pintype "passive"))
    )
    (net (code "88") (name "unconnected-(U16-NC-Pad29)") (class "Default")
      (node (ref "U16") (pin "29") (pinfunction "NC_29") (pintype "passive"))
    )
    (net (code "89") (name "unconnected-(U16-NC-Pad62)") (class "Default")
      (node (ref "U16") (pin "62") (pinfunction "NC_62") (pintype "passive"))
    )
    (net (code "90") (name "unconnected-(U16-NC-Pad64)") (class "Default")
      (node (ref "U16") (pin "64") (pinfunction "NC_64") (pintype "passive"))
    )
    (net (code "91") (name "unconnected-(U16-OPAMPN-Pad61)") (class "Default")
      (node (ref "U16") (pin "61") (pinfunction "OPAMPN_61") (pintype "input+no_connect"))
    )
    (net (code "92") (name "unconnected-(U16-OPAMPOUT-Pad63)") (class "Default")
      (node (ref "U16") (pin "63") (pinfunction "OPAMPOUT_63") (pintype "output+no_connect"))
    )
    (net (code "93") (name "unconnected-(U16-OPAMPP-Pad60)") (class "Default")
      (node (ref "U16") (pin "60") (pinfunction "OPAMPP_60") (pintype "input+no_connect"))
    )
  )
)
